# MotorDrivers.net
KiCad netlist of a schematic drawn in Altium Designer
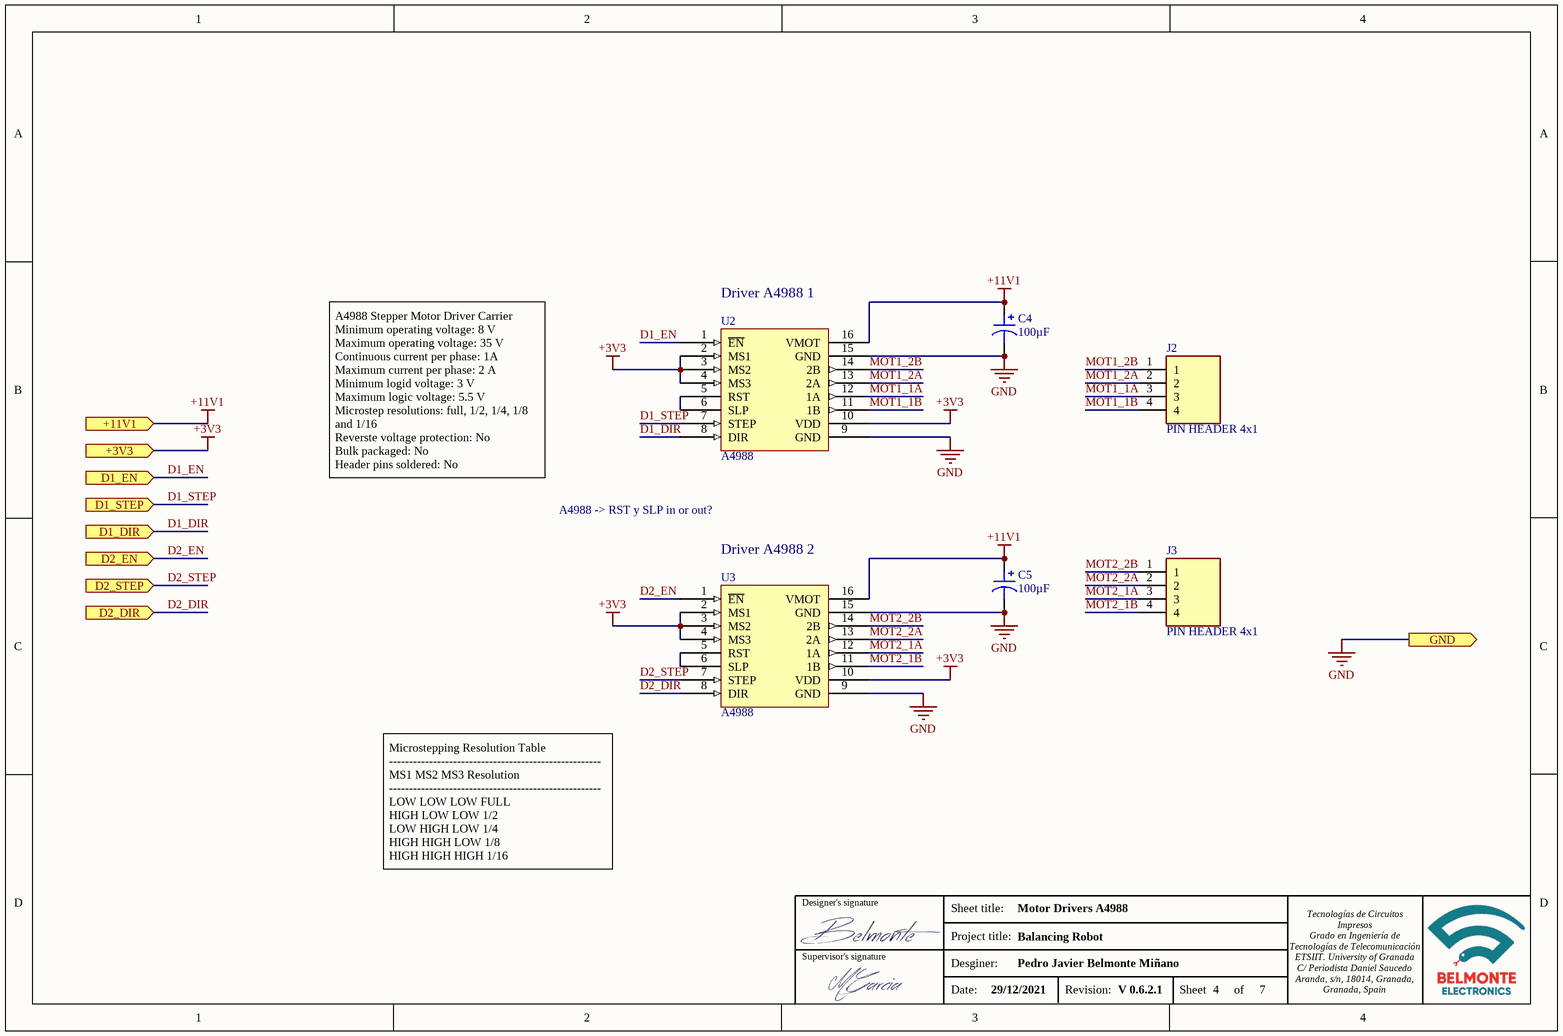
[diagram p0: MotorDrivers.SchDoc]

(export (version "E")
  (design (tool "Eeschema 10.0.6"))
  (components
    (comp (ref "C4")
      (value "ALUM 100uF")
      (footprint "CAP ALSMD POLY 5.3MM H6.1MM")
      (description "CAP ALUM 100UF 4V 2000H")
      (fields
        (field (name "PART NUMBER") "MAL218497352E3")
        (field (name "MANUFACTURER") "Vishay Beyschlag/Draloric/BC Components")
        (field (name "CAPACITANCE") "100µF")
      )
      (libsource (lib "ControlBoard") (part "MAL218497352E3"))
    )
    (comp (ref "C5")
      (value "ALUM 100uF")
      (footprint "CAP ALSMD POLY 5.3MM H6.1MM")
      (description "CAP ALUM 100UF 4V 2000H")
      (fields
        (field (name "PART NUMBER") "MAL218497352E3")
        (field (name "MANUFACTURER") "Vishay Beyschlag/Draloric/BC Components")
        (field (name "CAPACITANCE") "100µF")
      )
      (libsource (lib "ControlBoard") (part "MAL218497352E3"))
    )
    (comp (ref "J2")
      (value "PIN HEADER 4x1")
      (footprint "HDRV4W50P0X200_1X4_800X200X525P")
      (description "Connector")
      (fields
        (field (name "MANUFACTURER_PART_NUMBER") "M22-2510405")
        (field (name "MOUSER PART NUMBER") "855-M22-2510405")
      )
      (libsource (lib "ControlBoard") (part "M22-2510405"))
    )
    (comp (ref "J3")
      (value "PIN HEADER 4x1")
      (footprint "HDRV4W50P0X200_1X4_800X200X525P")
      (description "Connector")
      (fields
        (field (name "MANUFACTURER_PART_NUMBER") "M22-2510405")
        (field (name "MOUSER PART NUMBER") "855-M22-2510405")
      )
      (libsource (lib "ControlBoard") (part "M22-2510405"))
    )
    (comp (ref "U2")
      (value "A4988")
      (footprint "A4988")
      (description "Pololu A4988 Stepper Motor Driver Carrier")
      (libsource (lib "ControlBoard") (part "A4988"))
    )
    (comp (ref "U3")
      (value "A4988")
      (footprint "A4988")
      (description "Pololu A4988 Stepper Motor Driver Carrier")
      (libsource (lib "ControlBoard") (part "A4988"))
    )
  )
  (nets
    (net (code "1") (name "+3V3") (class "Default")
      (node (ref "U2") (pin "10") (pinfunction "VDD_10") (pintype "power_in"))
      (node (ref "U2") (pin "2") (pinfunction "MS1_2") (pintype "input"))
      (node (ref "U2") (pin "3") (pinfunction "MS2_3") (pintype "input"))
      (node (ref "U2") (pin "4") (pinfunction "MS3_4") (pintype "input"))
      (node (ref "U3") (pin "10") (pinfunction "VDD_10") (pintype "power_in"))
      (node (ref "U3") (pin "2") (pinfunction "MS1_2") (pintype "input"))
      (node (ref "U3") (pin "3") (pinfunction "MS2_3") (pintype "input"))
      (node (ref "U3") (pin "4") (pinfunction "MS3_4") (pintype "input"))
    )
    (net (code "2") (name "+11V1") (class "Default")
      (node (ref "C4") (pin "1") (pinfunction "1_1") (pintype "passive"))
      (node (ref "C5") (pin "1") (pinfunction "1_1") (pintype "passive"))
      (node (ref "U2") (pin "16") (pinfunction "VMOT_16") (pintype "power_in"))
      (node (ref "U3") (pin "16") (pinfunction "VMOT_16") (pintype "power_in"))
    )
    (net (code "3") (name "/D1_DIR") (class "Default")
      (node (ref "U2") (pin "8") (pinfunction "DIR_8") (pintype "input"))
    )
    (net (code "4") (name "/D1_EN") (class "Default")
      (node (ref "U2") (pin "1") (pinfunction "~{EN}_1") (pintype "input"))
    )
    (net (code "5") (name "/D1_STEP") (class "Default")
      (node (ref "U2") (pin "7") (pinfunction "STEP_7") (pintype "input"))
    )
    (net (code "6") (name "/D2_DIR") (class "Default")
      (node (ref "U3") (pin "8") (pinfunction "DIR_8") (pintype "input"))
    )
    (net (code "7") (name "/D2_EN") (class "Default")
      (node (ref "U3") (pin "1") (pinfunction "~{EN}_1") (pintype "input"))
    )
    (net (code "8") (name "/D2_STEP") (class "Default")
      (node (ref "U3") (pin "7") (pinfunction "STEP_7") (pintype "input"))
    )
    (net (code "9") (name "/MOT1_1A") (class "Default")
      (node (ref "J2") (pin "3") (pinfunction "3_3") (pintype "passive"))
      (node (ref "U2") (pin "12") (pinfunction "1A_12") (pintype "output"))
    )
    (net (code "10") (name "/MOT1_1B") (class "Default")
      (node (ref "J2") (pin "4") (pinfunction "4_4") (pintype "passive"))
      (node (ref "U2") (pin "11") (pinfunction "1B_11") (pintype "output"))
    )
    (net (code "11") (name "/MOT1_2A") (class "Default")
      (node (ref "J2") (pin "2") (pinfunction "2_2") (pintype "passive"))
      (node (ref "U2") (pin "13") (pinfunction "2A_13") (pintype "output"))
    )
    (net (code "12") (name "/MOT1_2B") (class "Default")
      (node (ref "J2") (pin "1") (pinfunction "1_1") (pintype "passive"))
      (node (ref "U2") (pin "14") (pinfunction "2B_14") (pintype "output"))
    )
    (net (code "13") (name "/MOT2_1A") (class "Default")
      (node (ref "J3") (pin "3") (pinfunction "3_3") (pintype "passive"))
      (node (ref "U3") (pin "12") (pinfunction "1A_12") (pintype "output"))
    )
    (net (code "14") (name "/MOT2_1B") (class "Default")
      (node (ref "J3") (pin "4") (pinfunction "4_4") (pintype "passive"))
      (node (ref "U3") (pin "11") (pinfunction "1B_11") (pintype "output"))
    )
    (net (code "15") (name "/MOT2_2A") (class "Default")
      (node (ref "J3") (pin "2") (pinfunction "2_2") (pintype "passive"))
      (node (ref "U3") (pin "13") (pinfunction "2A_13") (pintype "output"))
    )
    (net (code "16") (name "/MOT2_2B") (class "Default")
      (node (ref "J3") (pin "1") (pinfunction "1_1") (pintype "passive"))
      (node (ref "U3") (pin "14") (pinfunction "2B_14") (pintype "output"))
    )
    (net (code "17") (name "GND") (class "Default")
      (node (ref "C4") (pin "2") (pinfunction "2_2") (pintype "passive"))
      (node (ref "C5") (pin "2") (pinfunction "2_2") (pintype "passive"))
      (node (ref "U2") (pin "15") (pinfunction "GND_15") (pintype "power_in"))
      (node (ref "U2") (pin "9") (pinfunction "GND_9") (pintype "power_in"))
      (node (ref "U3") (pin "15") (pinfunction "GND_15") (pintype "power_in"))
      (node (ref "U3") (pin "9") (pinfunction "GND_9") (pintype "power_in"))
    )
    (net (code "18") (name "Net-(U2-RST)") (class "Default")
      (node (ref "U2") (pin "5") (pinfunction "RST_5") (pintype "passive"))
      (node (ref "U2") (pin "6") (pinfunction "SLP_6") (pintype "passive"))
    )
    (net (code "19") (name "Net-(U3-RST)") (class "Default")
      (node (ref "U3") (pin "5") (pinfunction "RST_5") (pintype "passive"))
      (node (ref "U3") (pin "6") (pinfunction "SLP_6") (pintype "passive"))
    )
  )
)
